# Telemetry_layoutmain.net
KiCad netlist of a schematic drawn in EAGLE
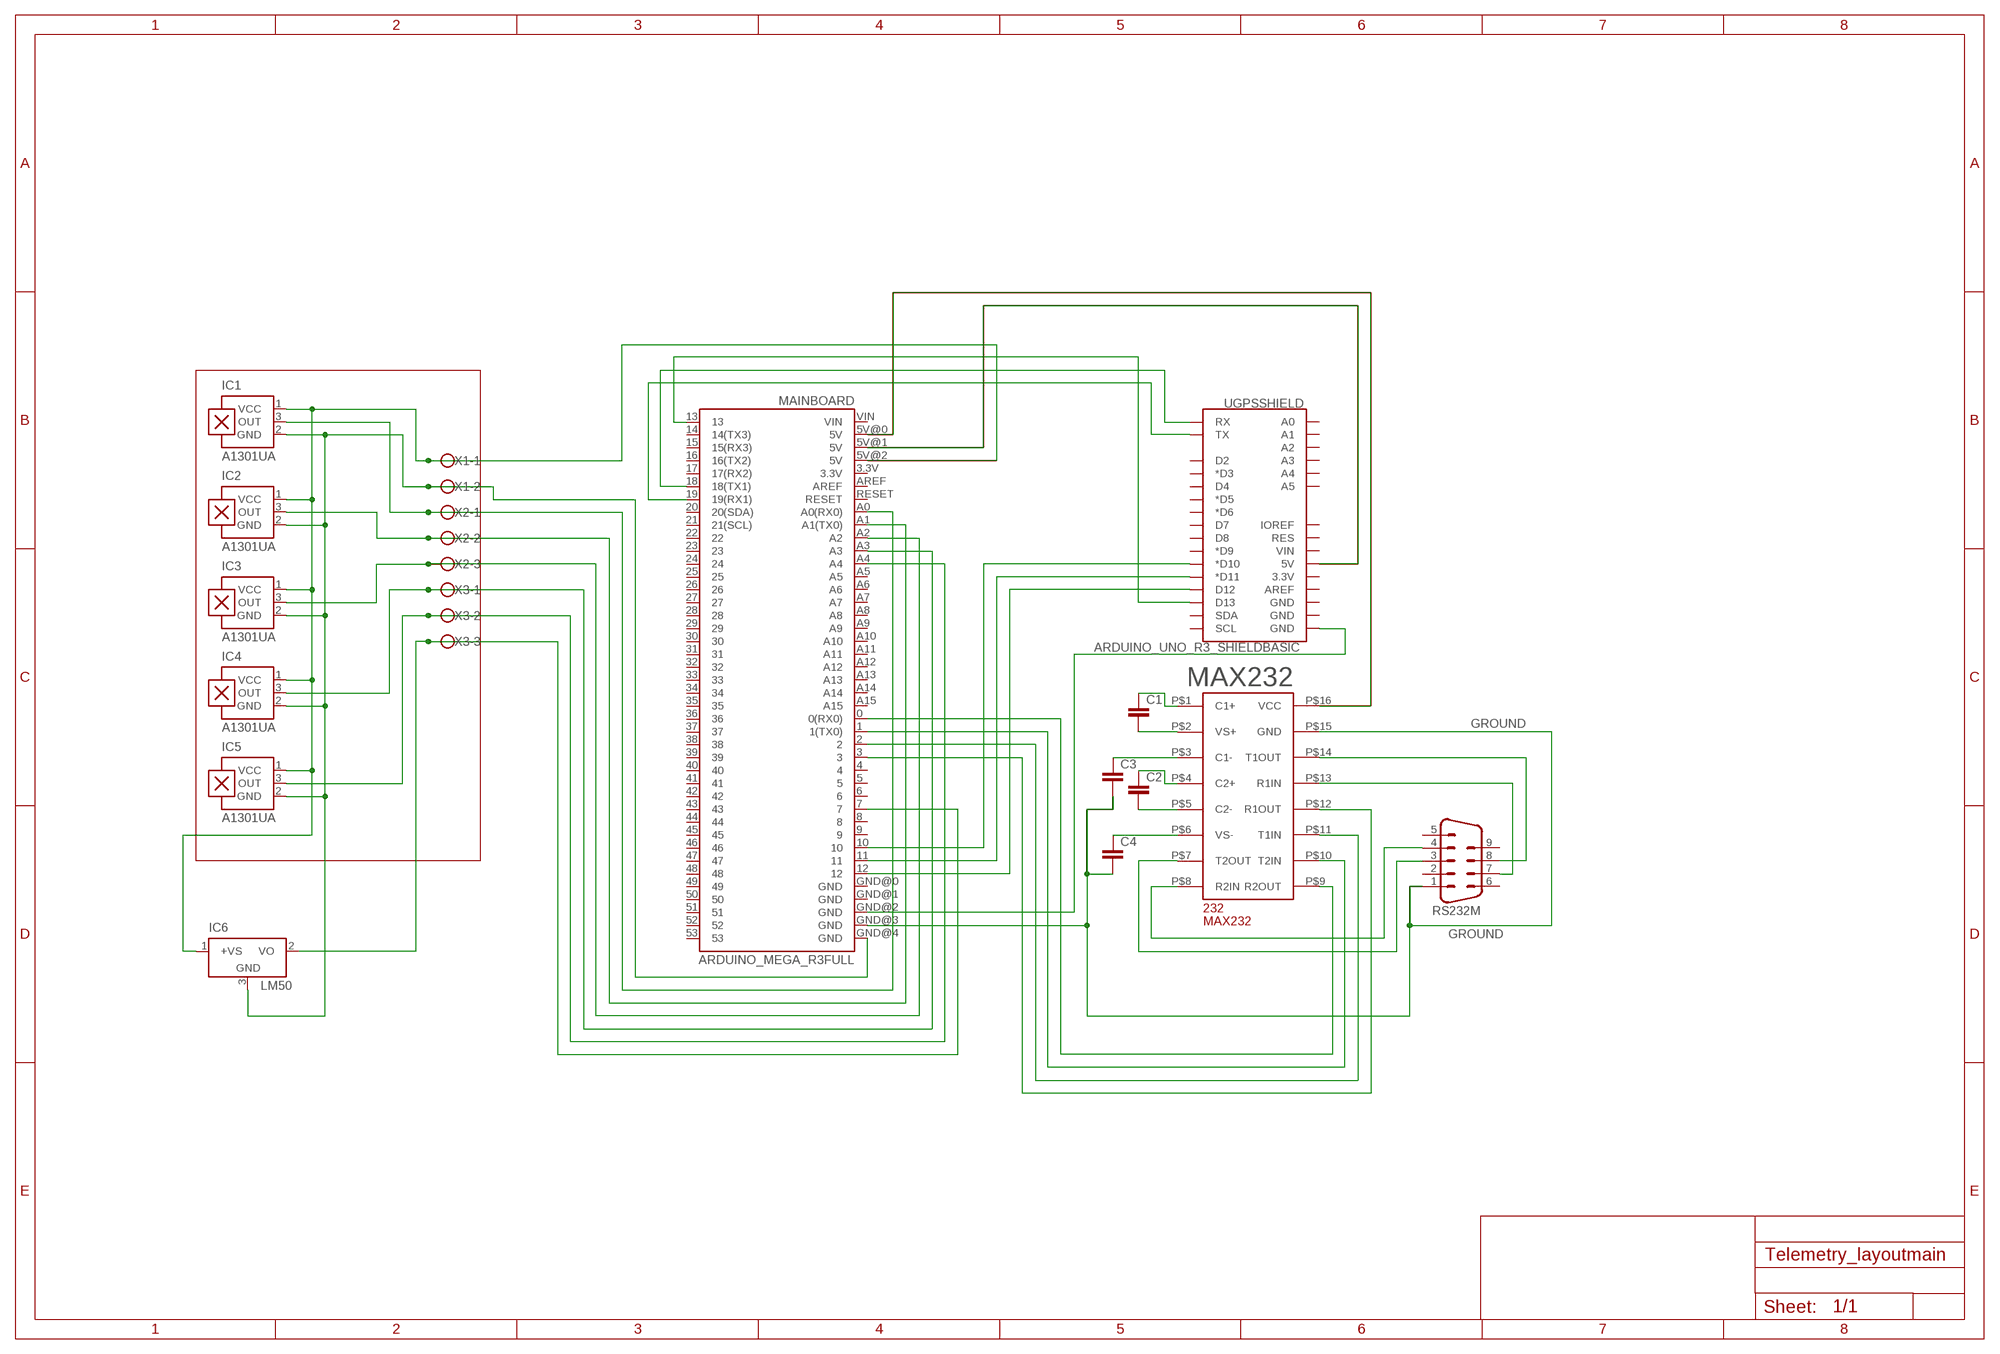
[diagram p0: schematic, sheet 1]

(export (version "E")
  (design (tool "Eeschema 10.0.6"))
  (components
    (comp (ref "232")
      (value "MAX232TELE")
      (footprint "eagle-import:DIP16")
      (libsource (lib "eagle-import") (part "MAX232TELE"))
    )
    (comp (ref "C1")
      (value "C2,5-3")
      (footprint "eagle-import:C2.5-3")
      (libsource (lib "eagle-import") (part "C2,5-3"))
    )
    (comp (ref "C2")
      (value "C2,5-3")
      (footprint "eagle-import:C2.5-3")
      (libsource (lib "eagle-import") (part "C2,5-3"))
    )
    (comp (ref "C3")
      (value "C2,5-3")
      (footprint "eagle-import:C2.5-3")
      (libsource (lib "eagle-import") (part "C2,5-3"))
    )
    (comp (ref "C4")
      (value "C2,5-3")
      (footprint "eagle-import:C2.5-3")
      (libsource (lib "eagle-import") (part "C2,5-3"))
    )
    (comp (ref "IC1")
      (value "A1301UA")
      (footprint "eagle-import:SIP3-UA")
      (fields (field (name "MF") "ALLEGRO MICROSYSTEMS, INC.") (field (name "MPN") "A1301EUA-T"))
      (libsource (lib "eagle-import") (part "A13?UA01"))
    )
    (comp (ref "IC2")
      (value "A1301UA")
      (footprint "eagle-import:SIP3-UA")
      (fields (field (name "MF") "ALLEGRO MICROSYSTEMS, INC.") (field (name "MPN") "A1301EUA-T"))
      (libsource (lib "eagle-import") (part "A13?UA01"))
    )
    (comp (ref "IC3")
      (value "A1301UA")
      (footprint "eagle-import:SIP3-UA")
      (fields (field (name "MF") "ALLEGRO MICROSYSTEMS, INC.") (field (name "MPN") "A1301EUA-T"))
      (libsource (lib "eagle-import") (part "A13?UA01"))
    )
    (comp (ref "IC4")
      (value "A1301UA")
      (footprint "eagle-import:SIP3-UA")
      (fields (field (name "MF") "ALLEGRO MICROSYSTEMS, INC.") (field (name "MPN") "A1301EUA-T"))
      (libsource (lib "eagle-import") (part "A13?UA01"))
    )
    (comp (ref "IC5")
      (value "A1301UA")
      (footprint "eagle-import:SIP3-UA")
      (fields (field (name "MF") "ALLEGRO MICROSYSTEMS, INC.") (field (name "MPN") "A1301EUA-T"))
      (libsource (lib "eagle-import") (part "A13?UA01"))
    )
    (comp (ref "IC6")
      (value "LM50")
      (footprint "eagle-import:SOT23")
      (libsource (lib "eagle-import") (part "LM50"))
    )
    (comp (ref "MAINBOARD")
      (value "ARDUINO_MEGA_R3FULL")
      (footprint "eagle-import:ARDUINO_MEGA")
      (libsource (lib "eagle-import") (part "ARDUINO_MEGA_R3FULL"))
    )
    (comp (ref "RS232M")
      (value "M09HP")
      (footprint "eagle-import:M09HP")
      (libsource (lib "eagle-import") (part "M09HP"))
    )
    (comp (ref "UGPSSHIELD")
      (value "ARDUINO_UNO_R3_SHIELDBASIC")
      (footprint "eagle-import:UNO_R3_SHIELD")
      (libsource (lib "eagle-import") (part "ARDUINO_UNO_R3_SHIELDBASIC"))
    )
    (comp (ref "X1")
      (value "W237-102")
      (footprint "eagle-import:W237-102")
      (fields (field (name "MPN") "237-102"))
      (libsource (lib "eagle-import") (part "W237-102"))
    )
    (comp (ref "X2")
      (value "W237-103")
      (footprint "eagle-import:W237-103")
      (fields (field (name "MPN") "237-103"))
      (libsource (lib "eagle-import") (part "W237-103"))
    )
    (comp (ref "X3")
      (value "W237-103")
      (footprint "eagle-import:W237-103")
      (fields (field (name "MPN") "237-103"))
      (libsource (lib "eagle-import") (part "W237-103"))
    )
  )
  (nets
    (net (code "1") (name "/GROUND") (class "Default")
      (node (ref "232") (pin "P$15") (pinfunction "GND_P$15") (pintype "bidirectional"))
      (node (ref "C3") (pin "2") (pinfunction "2_2") (pintype "passive"))
      (node (ref "C4") (pin "2") (pinfunction "2_2") (pintype "passive"))
      (node (ref "MAINBOARD") (pin "GND@3") (pinfunction "GND_GND@3") (pintype "bidirectional"))
      (node (ref "RS232M") (pin "1") (pinfunction "1_1") (pintype "passive"))
    )
    (net (code "2") (name "Net-(232-C1+)") (class "Default")
      (node (ref "232") (pin "P$1") (pinfunction "C1+_P$1") (pintype "bidirectional"))
      (node (ref "C1") (pin "1") (pinfunction "1_1") (pintype "passive"))
    )
    (net (code "3") (name "Net-(232-C1-)") (class "Default")
      (node (ref "232") (pin "P$3") (pinfunction "C1-_P$3") (pintype "bidirectional"))
      (node (ref "C3") (pin "1") (pinfunction "1_1") (pintype "passive"))
    )
    (net (code "4") (name "Net-(232-C2+)") (class "Default")
      (node (ref "232") (pin "P$4") (pinfunction "C2+_P$4") (pintype "bidirectional"))
      (node (ref "C2") (pin "1") (pinfunction "1_1") (pintype "passive"))
    )
    (net (code "5") (name "Net-(232-C2-)") (class "Default")
      (node (ref "232") (pin "P$5") (pinfunction "C2-_P$5") (pintype "bidirectional"))
      (node (ref "C2") (pin "2") (pinfunction "2_2") (pintype "passive"))
    )
    (net (code "6") (name "Net-(232-R1IN)") (class "Default")
      (node (ref "232") (pin "P$13") (pinfunction "R1IN_P$13") (pintype "bidirectional"))
      (node (ref "RS232M") (pin "7") (pinfunction "7_7") (pintype "passive"))
    )
    (net (code "7") (name "Net-(232-R1OUT)") (class "Default")
      (node (ref "232") (pin "P$12") (pinfunction "R1OUT_P$12") (pintype "bidirectional"))
      (node (ref "MAINBOARD") (pin "3") (pinfunction "3_3") (pintype "bidirectional"))
    )
    (net (code "8") (name "Net-(232-R2IN)") (class "Default")
      (node (ref "232") (pin "P$8") (pinfunction "R2IN_P$8") (pintype "bidirectional"))
      (node (ref "RS232M") (pin "4") (pinfunction "4_4") (pintype "passive"))
    )
    (net (code "9") (name "Net-(232-R2OUT)") (class "Default")
      (node (ref "232") (pin "P$9") (pinfunction "R2OUT_P$9") (pintype "bidirectional"))
      (node (ref "MAINBOARD") (pin "0") (pinfunction "0(RX0)_0") (pintype "bidirectional"))
    )
    (net (code "10") (name "Net-(232-T1IN)") (class "Default")
      (node (ref "232") (pin "P$11") (pinfunction "T1IN_P$11") (pintype "bidirectional"))
      (node (ref "MAINBOARD") (pin "2") (pinfunction "2_2") (pintype "bidirectional"))
    )
    (net (code "11") (name "Net-(232-T1OUT)") (class "Default")
      (node (ref "232") (pin "P$14") (pinfunction "T1OUT_P$14") (pintype "bidirectional"))
      (node (ref "RS232M") (pin "8") (pinfunction "8_8") (pintype "passive"))
    )
    (net (code "12") (name "Net-(232-T2IN)") (class "Default")
      (node (ref "232") (pin "P$10") (pinfunction "T2IN_P$10") (pintype "bidirectional"))
      (node (ref "MAINBOARD") (pin "1") (pinfunction "1(TX0)_1") (pintype "bidirectional"))
    )
    (net (code "13") (name "Net-(232-T2OUT)") (class "Default")
      (node (ref "232") (pin "P$7") (pinfunction "T2OUT_P$7") (pintype "bidirectional"))
      (node (ref "RS232M") (pin "3") (pinfunction "3_3") (pintype "passive"))
    )
    (net (code "14") (name "Net-(232-VCC)") (class "Default")
      (node (ref "232") (pin "P$16") (pinfunction "VCC_P$16") (pintype "bidirectional"))
      (node (ref "MAINBOARD") (pin "5V@0") (pinfunction "5V_5V@0") (pintype "bidirectional"))
    )
    (net (code "15") (name "Net-(232-VS+)") (class "Default")
      (node (ref "232") (pin "P$2") (pinfunction "VS+_P$2") (pintype "bidirectional"))
      (node (ref "C1") (pin "2") (pinfunction "2_2") (pintype "passive"))
    )
    (net (code "16") (name "Net-(232-VS-)") (class "Default")
      (node (ref "232") (pin "P$6") (pinfunction "VS-_P$6") (pintype "bidirectional"))
      (node (ref "C4") (pin "1") (pinfunction "1_1") (pintype "passive"))
    )
    (net (code "17") (name "Net-(IC1-GND)") (class "Default")
      (node (ref "IC1") (pin "2") (pinfunction "GND_2") (pintype "power_in"))
      (node (ref "IC2") (pin "2") (pinfunction "GND_2") (pintype "power_in"))
      (node (ref "IC3") (pin "2") (pinfunction "GND_2") (pintype "power_in"))
      (node (ref "IC4") (pin "2") (pinfunction "GND_2") (pintype "power_in"))
      (node (ref "IC5") (pin "2") (pinfunction "GND_2") (pintype "power_in"))
      (node (ref "IC6") (pin "3") (pinfunction "GND_3") (pintype "power_in"))
      (node (ref "MAINBOARD") (pin "GND@4") (pinfunction "GND_GND@4") (pintype "bidirectional"))
      (node (ref "X1") (pin "2") (pinfunction "KL_2") (pintype "passive"))
    )
    (net (code "18") (name "Net-(IC1-OUT)") (class "Default")
      (node (ref "IC1") (pin "3") (pinfunction "OUT_3") (pintype "output"))
      (node (ref "MAINBOARD") (pin "A0") (pinfunction "A0(RX0)_A0") (pintype "bidirectional"))
      (node (ref "X2") (pin "1") (pinfunction "KL_1") (pintype "passive"))
    )
    (net (code "19") (name "Net-(IC1-VCC)") (class "Default")
      (node (ref "IC1") (pin "1") (pinfunction "VCC_1") (pintype "power_in"))
      (node (ref "IC2") (pin "1") (pinfunction "VCC_1") (pintype "power_in"))
      (node (ref "IC3") (pin "1") (pinfunction "VCC_1") (pintype "power_in"))
      (node (ref "IC4") (pin "1") (pinfunction "VCC_1") (pintype "power_in"))
      (node (ref "IC5") (pin "1") (pinfunction "VCC_1") (pintype "power_in"))
      (node (ref "IC6") (pin "1") (pinfunction "+VS_1") (pintype "input"))
      (node (ref "MAINBOARD") (pin "5V@2") (pinfunction "5V_5V@2") (pintype "bidirectional"))
      (node (ref "X1") (pin "1") (pinfunction "KL_1") (pintype "passive"))
    )
    (net (code "20") (name "Net-(IC2-OUT)") (class "Default")
      (node (ref "IC2") (pin "3") (pinfunction "OUT_3") (pintype "output"))
      (node (ref "MAINBOARD") (pin "A1") (pinfunction "A1(TX0)_A1") (pintype "bidirectional"))
      (node (ref "X2") (pin "2") (pinfunction "KL_2") (pintype "passive"))
    )
    (net (code "21") (name "Net-(IC3-OUT)") (class "Default")
      (node (ref "IC3") (pin "3") (pinfunction "OUT_3") (pintype "output"))
      (node (ref "MAINBOARD") (pin "A2") (pinfunction "A2_A2") (pintype "bidirectional"))
      (node (ref "X2") (pin "3") (pinfunction "KL_3") (pintype "passive"))
    )
    (net (code "22") (name "Net-(IC4-OUT)") (class "Default")
      (node (ref "IC4") (pin "3") (pinfunction "OUT_3") (pintype "output"))
      (node (ref "MAINBOARD") (pin "A3") (pinfunction "A3_A3") (pintype "bidirectional"))
      (node (ref "X3") (pin "1") (pinfunction "KL_1") (pintype "passive"))
    )
    (net (code "23") (name "Net-(IC5-OUT)") (class "Default")
      (node (ref "IC5") (pin "3") (pinfunction "OUT_3") (pintype "output"))
      (node (ref "MAINBOARD") (pin "A4") (pinfunction "A4_A4") (pintype "bidirectional"))
      (node (ref "X3") (pin "2") (pinfunction "KL_2") (pintype "passive"))
    )
    (net (code "24") (name "Net-(IC6-VO)") (class "Default")
      (node (ref "IC6") (pin "2") (pinfunction "VO_2") (pintype "input"))
      (node (ref "MAINBOARD") (pin "7") (pinfunction "7_7") (pintype "bidirectional"))
      (node (ref "X3") (pin "3") (pinfunction "KL_3") (pintype "passive"))
    )
    (net (code "25") (name "Net-(MAINBOARD-5V-Pad5V@1)") (class "Default")
      (node (ref "MAINBOARD") (pin "5V@1") (pinfunction "5V_5V@1") (pintype "bidirectional"))
      (node (ref "UGPSSHIELD") (pin "5V") (pinfunction "5V_5V") (pintype "bidirectional"))
    )
    (net (code "26") (name "Net-(MAINBOARD-18(TX1))") (class "Default")
      (node (ref "MAINBOARD") (pin "18") (pinfunction "18(TX1)_18") (pintype "bidirectional"))
      (node (ref "UGPSSHIELD") (pin "RX") (pinfunction "RX_RX") (pintype "bidirectional"))
    )
    (net (code "27") (name "Net-(MAINBOARD-19(RX1))") (class "Default")
      (node (ref "MAINBOARD") (pin "19") (pinfunction "19(RX1)_19") (pintype "bidirectional"))
      (node (ref "UGPSSHIELD") (pin "TX") (pinfunction "TX_TX") (pintype "bidirectional"))
    )
    (net (code "28") (name "Net-(MAINBOARD-GND-PadGND@2)") (class "Default")
      (node (ref "MAINBOARD") (pin "GND@2") (pinfunction "GND_GND@2") (pintype "bidirectional"))
      (node (ref "UGPSSHIELD") (pin "GND@0") (pinfunction "GND_GND@0") (pintype "bidirectional"))
    )
    (net (code "29") (name "Net-(MAINBOARD-Pad12)") (class "Default")
      (node (ref "MAINBOARD") (pin "12") (pinfunction "12_12") (pintype "bidirectional"))
      (node (ref "UGPSSHIELD") (pin "D12") (pinfunction "D12_D12") (pintype "bidirectional"))
    )
    (net (code "30") (name "Net-(MAINBOARD-Pad13)") (class "Default")
      (node (ref "MAINBOARD") (pin "13") (pinfunction "13_13") (pintype "bidirectional"))
      (node (ref "UGPSSHIELD") (pin "D13") (pinfunction "D13_D13") (pintype "bidirectional"))
    )
    (net (code "31") (name "Net-(UGPSSHIELD-*D10)") (class "Default")
      (node (ref "MAINBOARD") (pin "10") (pinfunction "10_10") (pintype "bidirectional"))
      (node (ref "UGPSSHIELD") (pin "D10") (pinfunction "*D10_D10") (pintype "bidirectional"))
    )
    (net (code "32") (name "Net-(UGPSSHIELD-*D11)") (class "Default")
      (node (ref "MAINBOARD") (pin "11") (pinfunction "11_11") (pintype "bidirectional"))
      (node (ref "UGPSSHIELD") (pin "D11") (pinfunction "*D11_D11") (pintype "bidirectional"))
    )
    (net (code "33") (name "unconnected-(MAINBOARD-14(TX3)-Pad14)") (class "Default")
      (node (ref "MAINBOARD") (pin "14") (pinfunction "14(TX3)_14") (pintype "bidirectional"))
    )
    (net (code "34") (name "unconnected-(MAINBOARD-15(RX3)-Pad15)") (class "Default")
      (node (ref "MAINBOARD") (pin "15") (pinfunction "15(RX3)_15") (pintype "bidirectional"))
    )
    (net (code "35") (name "unconnected-(MAINBOARD-16(TX2)-Pad16)") (class "Default")
      (node (ref "MAINBOARD") (pin "16") (pinfunction "16(TX2)_16") (pintype "bidirectional"))
    )
    (net (code "36") (name "unconnected-(MAINBOARD-17(RX2)-Pad17)") (class "Default")
      (node (ref "MAINBOARD") (pin "17") (pinfunction "17(RX2)_17") (pintype "bidirectional"))
    )
    (net (code "37") (name "unconnected-(MAINBOARD-20(SDA)-Pad20)") (class "Default")
      (node (ref "MAINBOARD") (pin "20") (pinfunction "20(SDA)_20") (pintype "bidirectional"))
    )
    (net (code "38") (name "unconnected-(MAINBOARD-21(SCL)-Pad21)") (class "Default")
      (node (ref "MAINBOARD") (pin "21") (pinfunction "21(SCL)_21") (pintype "bidirectional"))
    )
    (net (code "39") (name "unconnected-(MAINBOARD-GND-PadGND@0)") (class "Default")
      (node (ref "MAINBOARD") (pin "GND@0") (pinfunction "GND_GND@0") (pintype "bidirectional"))
    )
    (net (code "40") (name "unconnected-(MAINBOARD-GND-PadGND@1)") (class "Default")
      (node (ref "MAINBOARD") (pin "GND@1") (pinfunction "GND_GND@1") (pintype "bidirectional"))
    )
    (net (code "41") (name "unconnected-(MAINBOARD-Pad3.3V)") (class "Default")
      (node (ref "MAINBOARD") (pin "3.3V") (pinfunction "3.3V_3.3V") (pintype "bidirectional"))
    )
    (net (code "42") (name "unconnected-(MAINBOARD-Pad4)") (class "Default")
      (node (ref "MAINBOARD") (pin "4") (pinfunction "4_4") (pintype "bidirectional"))
    )
    (net (code "43") (name "unconnected-(MAINBOARD-Pad5)") (class "Default")
      (node (ref "MAINBOARD") (pin "5") (pinfunction "5_5") (pintype "bidirectional"))
    )
    (net (code "44") (name "unconnected-(MAINBOARD-Pad6)") (class "Default")
      (node (ref "MAINBOARD") (pin "6") (pinfunction "6_6") (pintype "bidirectional"))
    )
    (net (code "45") (name "unconnected-(MAINBOARD-Pad8)") (class "Default")
      (node (ref "MAINBOARD") (pin "8") (pinfunction "8_8") (pintype "bidirectional"))
    )
    (net (code "46") (name "unconnected-(MAINBOARD-Pad9)") (class "Default")
      (node (ref "MAINBOARD") (pin "9") (pinfunction "9_9") (pintype "bidirectional"))
    )
    (net (code "47") (name "unconnected-(MAINBOARD-Pad22)") (class "Default")
      (node (ref "MAINBOARD") (pin "22") (pinfunction "22_22") (pintype "bidirectional"))
    )
    (net (code "48") (name "unconnected-(MAINBOARD-Pad23)") (class "Default")
      (node (ref "MAINBOARD") (pin "23") (pinfunction "23_23") (pintype "bidirectional"))
    )
    (net (code "49") (name "unconnected-(MAINBOARD-Pad24)") (class "Default")
      (node (ref "MAINBOARD") (pin "24") (pinfunction "24_24") (pintype "bidirectional"))
    )
    (net (code "50") (name "unconnected-(MAINBOARD-Pad25)") (class "Default")
      (node (ref "MAINBOARD") (pin "25") (pinfunction "25_25") (pintype "bidirectional"))
    )
    (net (code "51") (name "unconnected-(MAINBOARD-Pad26)") (class "Default")
      (node (ref "MAINBOARD") (pin "26") (pinfunction "26_26") (pintype "bidirectional"))
    )
    (net (code "52") (name "unconnected-(MAINBOARD-Pad27)") (class "Default")
      (node (ref "MAINBOARD") (pin "27") (pinfunction "27_27") (pintype "bidirectional"))
    )
    (net (code "53") (name "unconnected-(MAINBOARD-Pad28)") (class "Default")
      (node (ref "MAINBOARD") (pin "28") (pinfunction "28_28") (pintype "bidirectional"))
    )
    (net (code "54") (name "unconnected-(MAINBOARD-Pad29)") (class "Default")
      (node (ref "MAINBOARD") (pin "29") (pinfunction "29_29") (pintype "bidirectional"))
    )
    (net (code "55") (name "unconnected-(MAINBOARD-Pad30)") (class "Default")
      (node (ref "MAINBOARD") (pin "30") (pinfunction "30_30") (pintype "bidirectional"))
    )
    (net (code "56") (name "unconnected-(MAINBOARD-Pad31)") (class "Default")
      (node (ref "MAINBOARD") (pin "31") (pinfunction "31_31") (pintype "bidirectional"))
    )
    (net (code "57") (name "unconnected-(MAINBOARD-Pad32)") (class "Default")
      (node (ref "MAINBOARD") (pin "32") (pinfunction "32_32") (pintype "bidirectional"))
    )
    (net (code "58") (name "unconnected-(MAINBOARD-Pad33)") (class "Default")
      (node (ref "MAINBOARD") (pin "33") (pinfunction "33_33") (pintype "bidirectional"))
    )
    (net (code "59") (name "unconnected-(MAINBOARD-Pad34)") (class "Default")
      (node (ref "MAINBOARD") (pin "34") (pinfunction "34_34") (pintype "bidirectional"))
    )
    (net (code "60") (name "unconnected-(MAINBOARD-Pad35)") (class "Default")
      (node (ref "MAINBOARD") (pin "35") (pinfunction "35_35") (pintype "bidirectional"))
    )
    (net (code "61") (name "unconnected-(MAINBOARD-Pad36)") (class "Default")
      (node (ref "MAINBOARD") (pin "36") (pinfunction "36_36") (pintype "bidirectional"))
    )
    (net (code "62") (name "unconnected-(MAINBOARD-Pad37)") (class "Default")
      (node (ref "MAINBOARD") (pin "37") (pinfunction "37_37") (pintype "bidirectional"))
    )
    (net (code "63") (name "unconnected-(MAINBOARD-Pad38)") (class "Default")
      (node (ref "MAINBOARD") (pin "38") (pinfunction "38_38") (pintype "bidirectional"))
    )
    (net (code "64") (name "unconnected-(MAINBOARD-Pad39)") (class "Default")
      (node (ref "MAINBOARD") (pin "39") (pinfunction "39_39") (pintype "bidirectional"))
    )
    (net (code "65") (name "unconnected-(MAINBOARD-Pad40)") (class "Default")
      (node (ref "MAINBOARD") (pin "40") (pinfunction "40_40") (pintype "bidirectional"))
    )
    (net (code "66") (name "unconnected-(MAINBOARD-Pad41)") (class "Default")
      (node (ref "MAINBOARD") (pin "41") (pinfunction "41_41") (pintype "bidirectional"))
    )
    (net (code "67") (name "unconnected-(MAINBOARD-Pad42)") (class "Default")
      (node (ref "MAINBOARD") (pin "42") (pinfunction "42_42") (pintype "bidirectional"))
    )
    (net (code "68") (name "unconnected-(MAINBOARD-Pad43)") (class "Default")
      (node (ref "MAINBOARD") (pin "43") (pinfunction "43_43") (pintype "bidirectional"))
    )
    (net (code "69") (name "unconnected-(MAINBOARD-Pad44)") (class "Default")
      (node (ref "MAINBOARD") (pin "44") (pinfunction "44_44") (pintype "bidirectional"))
    )
    (net (code "70") (name "unconnected-(MAINBOARD-Pad45)") (class "Default")
      (node (ref "MAINBOARD") (pin "45") (pinfunction "45_45") (pintype "bidirectional"))
    )
    (net (code "71") (name "unconnected-(MAINBOARD-Pad46)") (class "Default")
      (node (ref "MAINBOARD") (pin "46") (pinfunction "46_46") (pintype "bidirectional"))
    )
    (net (code "72") (name "unconnected-(MAINBOARD-Pad47)") (class "Default")
      (node (ref "MAINBOARD") (pin "47") (pinfunction "47_47") (pintype "bidirectional"))
    )
    (net (code "73") (name "unconnected-(MAINBOARD-Pad48)") (class "Default")
      (node (ref "MAINBOARD") (pin "48") (pinfunction "48_48") (pintype "bidirectional"))
    )
    (net (code "74") (name "unconnected-(MAINBOARD-Pad49)") (class "Default")
      (node (ref "MAINBOARD") (pin "49") (pinfunction "49_49") (pintype "bidirectional"))
    )
    (net (code "75") (name "unconnected-(MAINBOARD-Pad50)") (class "Default")
      (node (ref "MAINBOARD") (pin "50") (pinfunction "50_50") (pintype "bidirectional"))
    )
    (net (code "76") (name "unconnected-(MAINBOARD-Pad51)") (class "Default")
      (node (ref "MAINBOARD") (pin "51") (pinfunction "51_51") (pintype "bidirectional"))
    )
    (net (code "77") (name "unconnected-(MAINBOARD-Pad52)") (class "Default")
      (node (ref "MAINBOARD") (pin "52") (pinfunction "52_52") (pintype "bidirectional"))
    )
    (net (code "78") (name "unconnected-(MAINBOARD-Pad53)") (class "Default")
      (node (ref "MAINBOARD") (pin "53") (pinfunction "53_53") (pintype "bidirectional"))
    )
    (net (code "79") (name "unconnected-(MAINBOARD-PadA5)") (class "Default")
      (node (ref "MAINBOARD") (pin "A5") (pinfunction "A5_A5") (pintype "bidirectional"))
    )
    (net (code "80") (name "unconnected-(MAINBOARD-PadA6)") (class "Default")
      (node (ref "MAINBOARD") (pin "A6") (pinfunction "A6_A6") (pintype "bidirectional"))
    )
    (net (code "81") (name "unconnected-(MAINBOARD-PadA7)") (class "Default")
      (node (ref "MAINBOARD") (pin "A7") (pinfunction "A7_A7") (pintype "bidirectional"))
    )
    (net (code "82") (name "unconnected-(MAINBOARD-PadA8)") (class "Default")
      (node (ref "MAINBOARD") (pin "A8") (pinfunction "A8_A8") (pintype "bidirectional"))
    )
    (net (code "83") (name "unconnected-(MAINBOARD-PadA9)") (class "Default")
      (node (ref "MAINBOARD") (pin "A9") (pinfunction "A9_A9") (pintype "bidirectional"))
    )
    (net (code "84") (name "unconnected-(MAINBOARD-PadA10)") (class "Default")
      (node (ref "MAINBOARD") (pin "A10") (pinfunction "A10_A10") (pintype "bidirectional"))
    )
    (net (code "85") (name "unconnected-(MAINBOARD-PadA11)") (class "Default")
      (node (ref "MAINBOARD") (pin "A11") (pinfunction "A11_A11") (pintype "bidirectional"))
    )
    (net (code "86") (name "unconnected-(MAINBOARD-PadA12)") (class "Default")
      (node (ref "MAINBOARD") (pin "A12") (pinfunction "A12_A12") (pintype "bidirectional"))
    )
    (net (code "87") (name "unconnected-(MAINBOARD-PadA13)") (class "Default")
      (node (ref "MAINBOARD") (pin "A13") (pinfunction "A13_A13") (pintype "bidirectional"))
    )
    (net (code "88") (name "unconnected-(MAINBOARD-PadA14)") (class "Default")
      (node (ref "MAINBOARD") (pin "A14") (pinfunction "A14_A14") (pintype "bidirectional"))
    )
    (net (code "89") (name "unconnected-(MAINBOARD-PadA15)") (class "Default")
      (node (ref "MAINBOARD") (pin "A15") (pinfunction "A15_A15") (pintype "bidirectional"))
    )
    (net (code "90") (name "unconnected-(MAINBOARD-PadAREF)") (class "Default")
      (node (ref "MAINBOARD") (pin "AREF") (pinfunction "AREF_AREF") (pintype "bidirectional"))
    )
    (net (code "91") (name "unconnected-(MAINBOARD-PadRESET)") (class "Default")
      (node (ref "MAINBOARD") (pin "RESET") (pinfunction "RESET_RESET") (pintype "bidirectional"))
    )
    (net (code "92") (name "unconnected-(MAINBOARD-PadVIN)") (class "Default")
      (node (ref "MAINBOARD") (pin "VIN") (pinfunction "VIN_VIN") (pintype "bidirectional"))
    )
    (net (code "93") (name "unconnected-(RS232M-Pad2)") (class "Default")
      (node (ref "RS232M") (pin "2") (pinfunction "2_2") (pintype "passive"))
    )
    (net (code "94") (name "unconnected-(RS232M-Pad5)") (class "Default")
      (node (ref "RS232M") (pin "5") (pinfunction "5_5") (pintype "passive"))
    )
    (net (code "95") (name "unconnected-(RS232M-Pad6)") (class "Default")
      (node (ref "RS232M") (pin "6") (pinfunction "6_6") (pintype "passive"))
    )
    (net (code "96") (name "unconnected-(RS232M-Pad9)") (class "Default")
      (node (ref "RS232M") (pin "9") (pinfunction "9_9") (pintype "passive"))
    )
    (net (code "97") (name "unconnected-(UGPSSHIELD-*D3-PadD3)") (class "Default")
      (node (ref "UGPSSHIELD") (pin "D3") (pinfunction "*D3_D3") (pintype "bidirectional"))
    )
    (net (code "98") (name "unconnected-(UGPSSHIELD-*D5-PadD5)") (class "Default")
      (node (ref "UGPSSHIELD") (pin "D5") (pinfunction "*D5_D5") (pintype "bidirectional"))
    )
    (net (code "99") (name "unconnected-(UGPSSHIELD-*D6-PadD6)") (class "Default")
      (node (ref "UGPSSHIELD") (pin "D6") (pinfunction "*D6_D6") (pintype "bidirectional"))
    )
    (net (code "100") (name "unconnected-(UGPSSHIELD-*D9-PadD9)") (class "Default")
      (node (ref "UGPSSHIELD") (pin "D9") (pinfunction "*D9_D9") (pintype "bidirectional"))
    )
    (net (code "101") (name "unconnected-(UGPSSHIELD-GND-PadGND@1)") (class "Default")
      (node (ref "UGPSSHIELD") (pin "GND@1") (pinfunction "GND_GND@1") (pintype "bidirectional"))
    )
    (net (code "102") (name "unconnected-(UGPSSHIELD-GND-PadGND@2)") (class "Default")
      (node (ref "UGPSSHIELD") (pin "GND@2") (pinfunction "GND_GND@2") (pintype "bidirectional"))
    )
    (net (code "103") (name "unconnected-(UGPSSHIELD-Pad3.3V)") (class "Default")
      (node (ref "UGPSSHIELD") (pin "3.3V") (pinfunction "3.3V_3.3V") (pintype "bidirectional"))
    )
    (net (code "104") (name "unconnected-(UGPSSHIELD-PadA0)") (class "Default")
      (node (ref "UGPSSHIELD") (pin "A0") (pinfunction "A0_A0") (pintype "bidirectional"))
    )
    (net (code "105") (name "unconnected-(UGPSSHIELD-PadA1)") (class "Default")
      (node (ref "UGPSSHIELD") (pin "A1") (pinfunction "A1_A1") (pintype "bidirectional"))
    )
    (net (code "106") (name "unconnected-(UGPSSHIELD-PadA2)") (class "Default")
      (node (ref "UGPSSHIELD") (pin "A2") (pinfunction "A2_A2") (pintype "bidirectional"))
    )
    (net (code "107") (name "unconnected-(UGPSSHIELD-PadA3)") (class "Default")
      (node (ref "UGPSSHIELD") (pin "A3") (pinfunction "A3_A3") (pintype "bidirectional"))
    )
    (net (code "108") (name "unconnected-(UGPSSHIELD-PadA4)") (class "Default")
      (node (ref "UGPSSHIELD") (pin "A4") (pinfunction "A4_A4") (pintype "bidirectional"))
    )
    (net (code "109") (name "unconnected-(UGPSSHIELD-PadA5)") (class "Default")
      (node (ref "UGPSSHIELD") (pin "A5") (pinfunction "A5_A5") (pintype "bidirectional"))
    )
    (net (code "110") (name "unconnected-(UGPSSHIELD-PadAREF)") (class "Default")
      (node (ref "UGPSSHIELD") (pin "AREF") (pinfunction "AREF_AREF") (pintype "bidirectional"))
    )
    (net (code "111") (name "unconnected-(UGPSSHIELD-PadD2)") (class "Default")
      (node (ref "UGPSSHIELD") (pin "D2") (pinfunction "D2_D2") (pintype "bidirectional"))
    )
    (net (code "112") (name "unconnected-(UGPSSHIELD-PadD4)") (class "Default")
      (node (ref "UGPSSHIELD") (pin "D4") (pinfunction "D4_D4") (pintype "bidirectional"))
    )
    (net (code "113") (name "unconnected-(UGPSSHIELD-PadD7)") (class "Default")
      (node (ref "UGPSSHIELD") (pin "D7") (pinfunction "D7_D7") (pintype "bidirectional"))
    )
    (net (code "114") (name "unconnected-(UGPSSHIELD-PadD8)") (class "Default")
      (node (ref "UGPSSHIELD") (pin "D8") (pinfunction "D8_D8") (pintype "bidirectional"))
    )
    (net (code "115") (name "unconnected-(UGPSSHIELD-PadIOREF)") (class "Default")
      (node (ref "UGPSSHIELD") (pin "IOREF") (pinfunction "IOREF_IOREF") (pintype "bidirectional"))
    )
    (net (code "116") (name "unconnected-(UGPSSHIELD-PadRES)") (class "Default")
      (node (ref "UGPSSHIELD") (pin "RES") (pinfunction "RES_RES") (pintype "bidirectional"))
    )
    (net (code "117") (name "unconnected-(UGPSSHIELD-PadSCL)") (class "Default")
      (node (ref "UGPSSHIELD") (pin "SCL") (pinfunction "SCL_SCL") (pintype "bidirectional"))
    )
    (net (code "118") (name "unconnected-(UGPSSHIELD-PadSDA)") (class "Default")
      (node (ref "UGPSSHIELD") (pin "SDA") (pinfunction "SDA_SDA") (pintype "bidirectional"))
    )
    (net (code "119") (name "unconnected-(UGPSSHIELD-PadVIN)") (class "Default")
      (node (ref "UGPSSHIELD") (pin "VIN") (pinfunction "VIN_VIN") (pintype "bidirectional"))
    )
  )
)
